# LCEDA.net
KiCad netlist of a schematic drawn in EasyEDA Pro
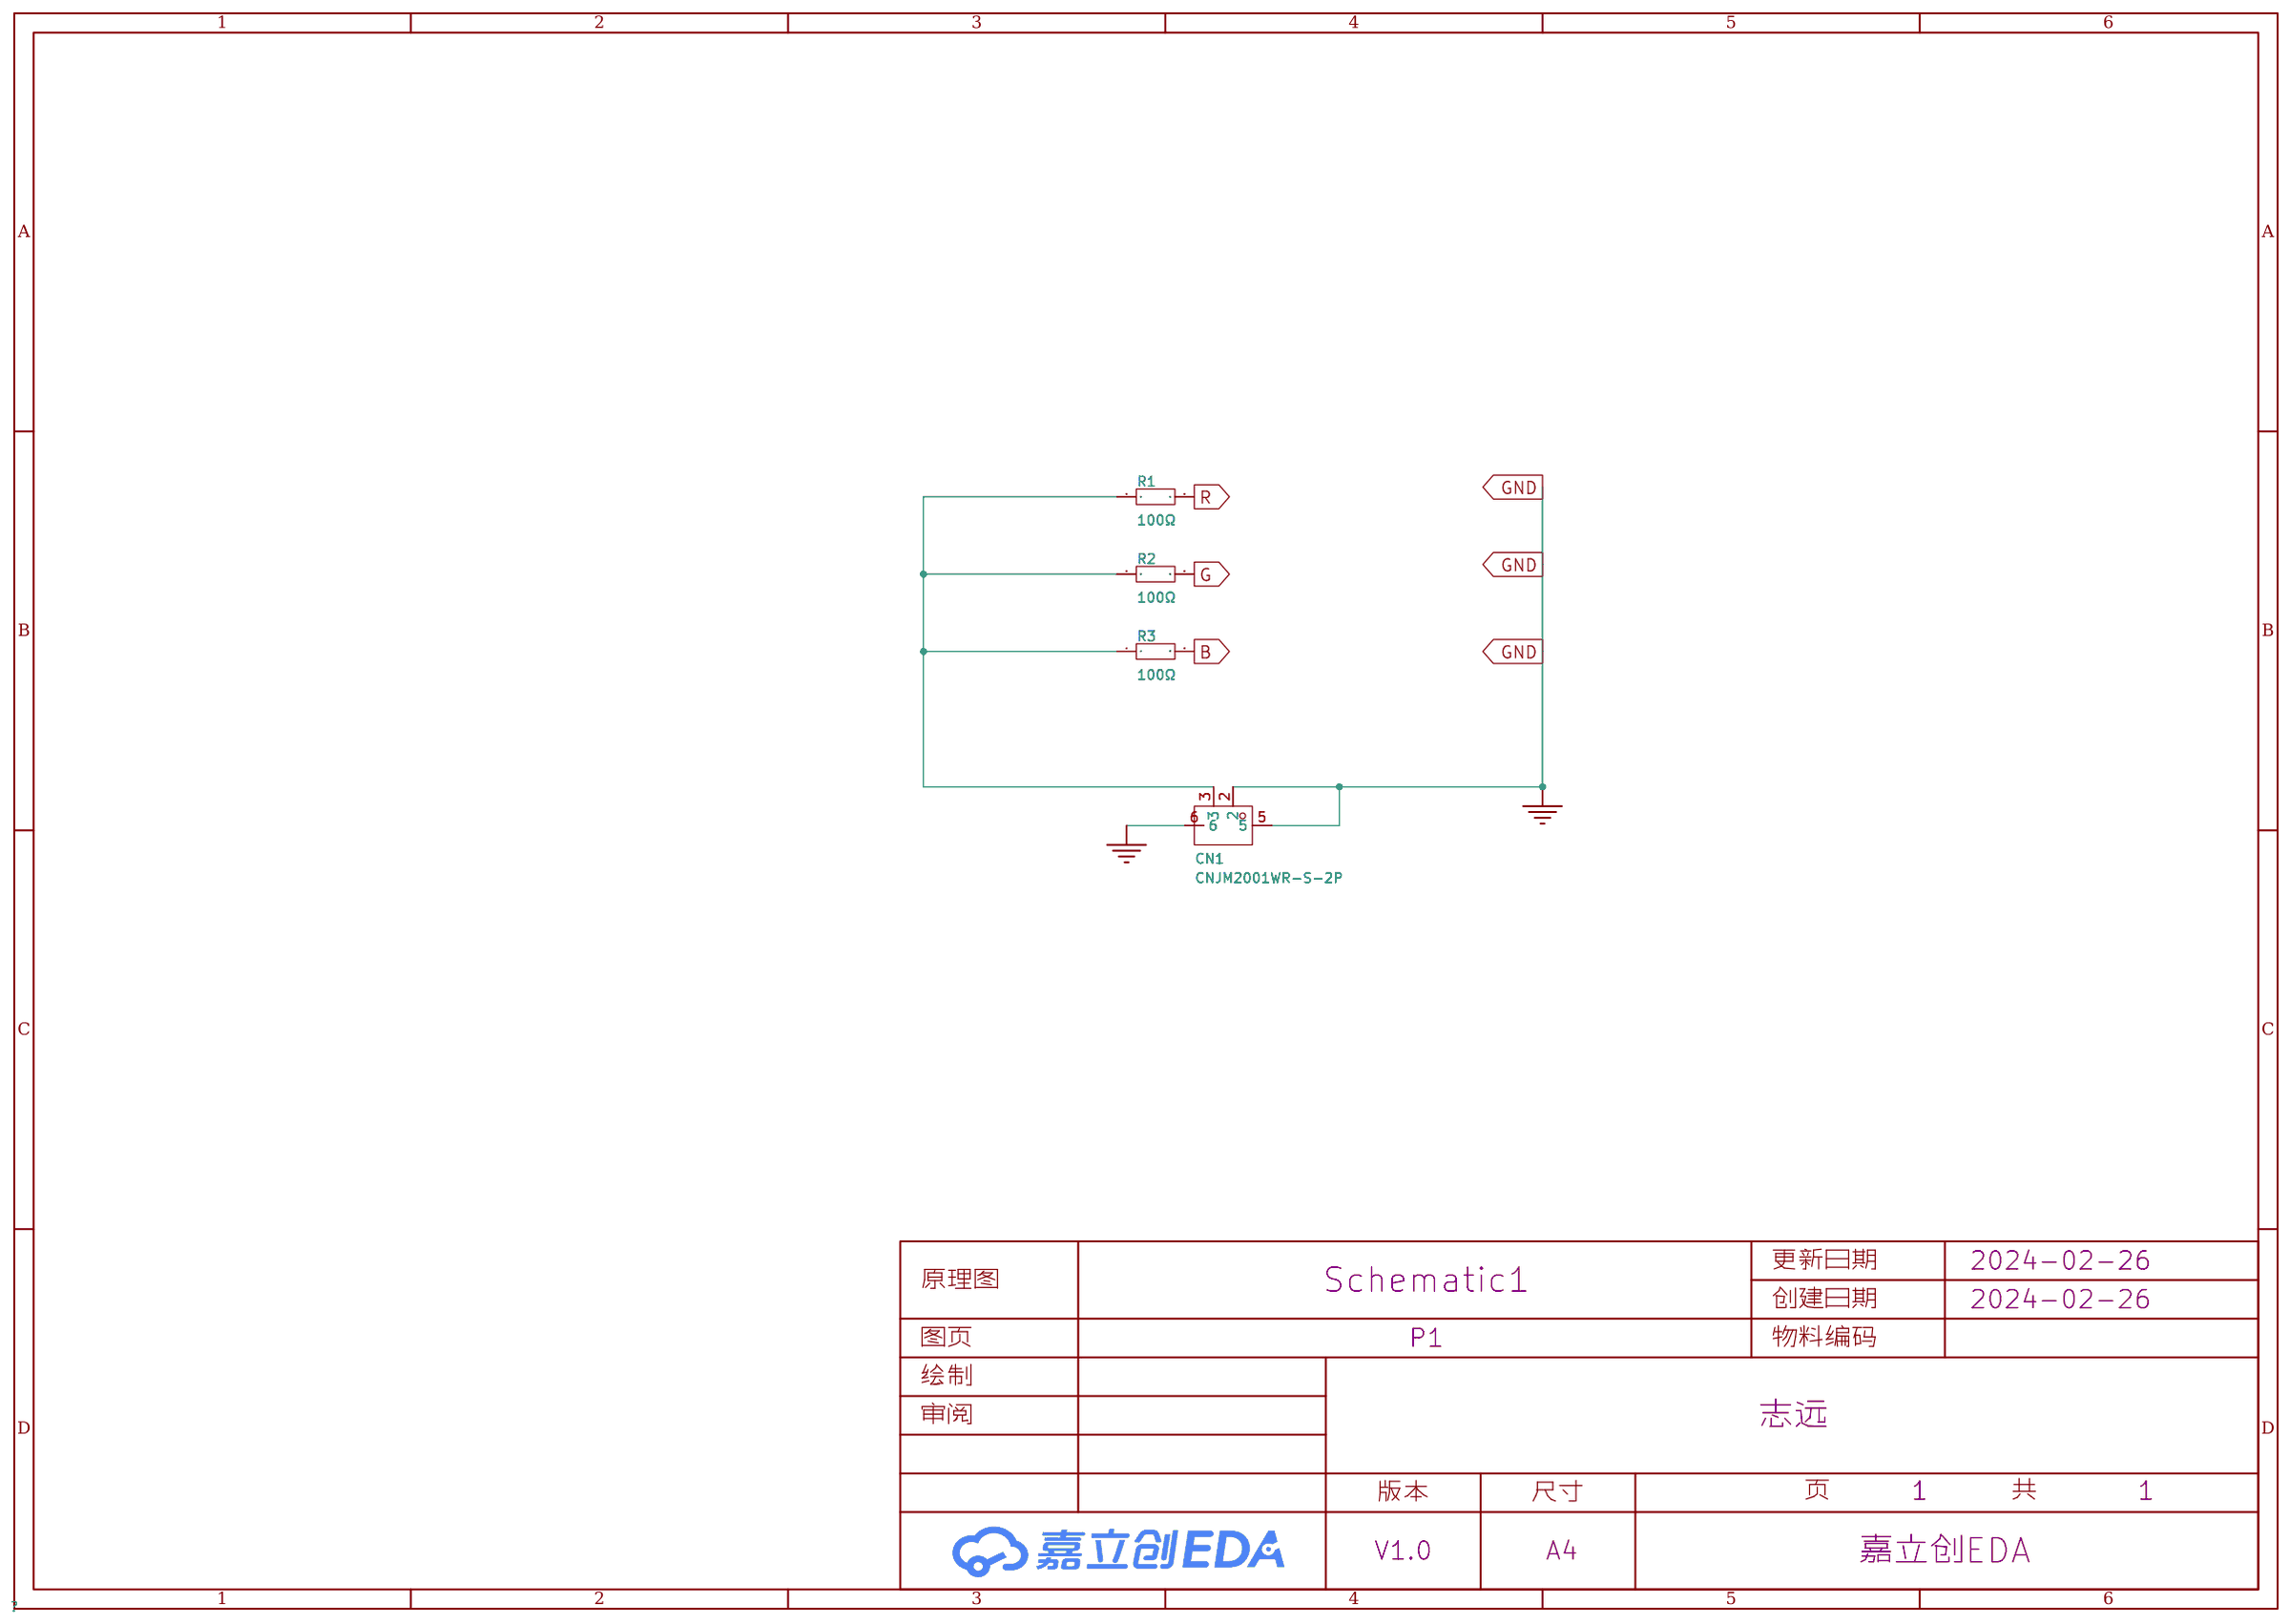
[diagram p0: schematic sheet]

(export (version "E")
  (design (tool "Eeschema 10.0.6"))
  (components
    (comp (ref "CN1")
      (value "CNJM2001WR-S-2P")
      (footprint "easyedapro:FPC-SMD_CNJM2001WR-S-2P")
      (fields (field (name "Manufacturer") "CNJM(九木精密)"))
      (libsource (lib "easyedapro") (part "CNJM2001WR-S-2P"))
    )
    (comp (ref "R1")
      (value "100Ω")
      (fields
        (field (name "Manufacturer Part") "1210W2F1000T5E")
        (field (name "Manufacturer") "UNI-ROYAL(厚声)")
      )
      (libsource (lib "easyedapro") (part "电阻"))
    )
    (comp (ref "R2")
      (value "100Ω")
      (fields
        (field (name "Manufacturer Part") "1210W2F1000T5E")
        (field (name "Manufacturer") "UNI-ROYAL(厚声)")
      )
      (libsource (lib "easyedapro") (part "电阻"))
    )
    (comp (ref "R3")
      (value "100Ω")
      (fields
        (field (name "Manufacturer Part") "1210W2F1000T5E")
        (field (name "Manufacturer") "UNI-ROYAL(厚声)")
      )
      (libsource (lib "easyedapro") (part "电阻"))
    )
  )
  (nets
    (net (code "1") (name "B") (class "Default")
      (node (ref "R3") (pin "2") (pinfunction "2_2") (pintype "input"))
    )
    (net (code "2") (name "G") (class "Default")
      (node (ref "R2") (pin "2") (pinfunction "2_2") (pintype "input"))
    )
    (net (code "3") (name "GND") (class "Default")
      (node (ref "CN1") (pin "2") (pinfunction "2_2") (pintype "input"))
      (node (ref "CN1") (pin "5") (pinfunction "5_5") (pintype "input"))
      (node (ref "CN1") (pin "6") (pinfunction "6_6") (pintype "input"))
    )
    (net (code "4") (name "Net-(CN1-Pad3)") (class "Default")
      (node (ref "CN1") (pin "3") (pinfunction "3_3") (pintype "input"))
      (node (ref "R1") (pin "1") (pinfunction "1_1") (pintype "input"))
      (node (ref "R2") (pin "1") (pinfunction "1_1") (pintype "input"))
      (node (ref "R3") (pin "1") (pinfunction "1_1") (pintype "input"))
    )
    (net (code "5") (name "R") (class "Default")
      (node (ref "R1") (pin "2") (pinfunction "2_2") (pintype "input"))
    )
  )
)
